# PowerSupply.net
KiCad netlist of a schematic drawn in Altium Designer
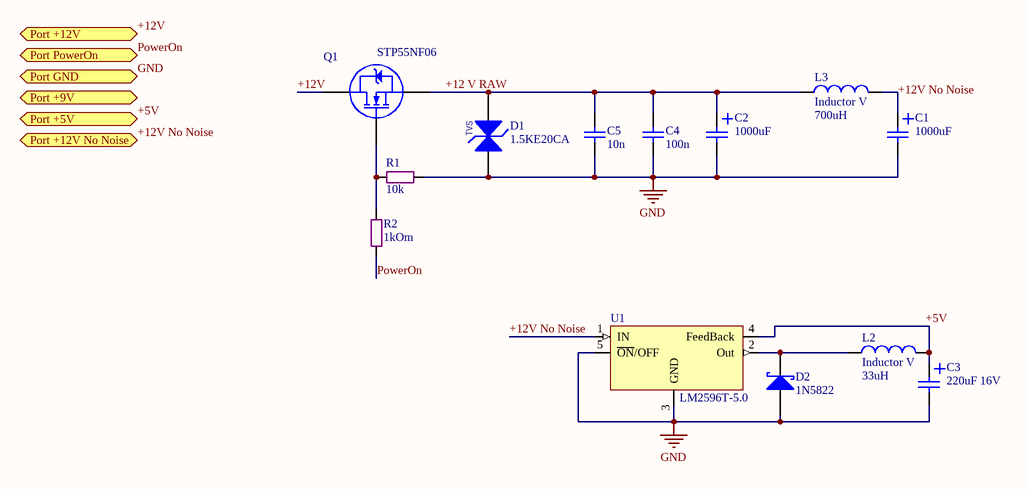
[diagram p0: PowerSupply.SchDoc]

(export (version "E")
  (design (tool "Eeschema 10.0.6"))
  (components
    (comp (ref "C1")
      (value "1000uF")
      (footprint "Capacitor:Cap E p5.08mm D10.2mm (3p)")
      (description "Capacitor")
      (libsource (lib "Capacitor") (part "Cap E 1000mF x 25V"))
    )
    (comp (ref "C2")
      (value "1000uF")
      (footprint "Capacitor:Cap E p5.08mm D10.2mm (3p)")
      (description "Capacitor")
      (libsource (lib "Capacitor") (part "Cap E 1000mF x 25V"))
    )
    (comp (ref "C3")
      (value "220uF 16V")
      (footprint "Capacitor:Cap E p2mm D6.5xH11")
      (description "Capacitor")
      (libsource (lib "Capacitor") (part "Cap E 220mF x 16V"))
    )
    (comp (ref "C4")
      (value "100n")
      (footprint "Capacitor:Cap P5.08MM (3p) disk2")
      (description "Capacitor")
      (libsource (lib "Capacitor") (part "Cap Ceramic"))
    )
    (comp (ref "C5")
      (value "10n")
      (footprint "Capacitor:Cap P5.08MM (3p) disk2")
      (description "Capacitor")
      (libsource (lib "Capacitor") (part "Cap Ceramic"))
    )
    (comp (ref "D1")
      (value "1.5KE20CA")
      (footprint "Diodes:TVS diode DO-201")
      (description "1500W Transil (TVS Diode)")
      (libsource (lib "Diodes") (part "TVS 1.5KE20CA"))
    )
    (comp (ref "D2")
      (value "1N5822")
      (footprint "Diodes:Diode DO-201")
      (description "3 Amp Shotki  Diode")
      (libsource (lib "Diodes") (part "D Shotki 1N5822"))
    )
    (comp (ref "L2")
      (value "Inductor V")
      (footprint "Transformers:Toroid V D14-W6")
      (description "Inductor Vertical")
      (fields (field (name "ALTIUM_VALUE") "33uH") (field (name "PUBLISHER") "Altium Limited"))
      (libsource (lib "Transformers") (part "Inductor V"))
    )
    (comp (ref "L3")
      (value "Inductor V")
      (footprint "Transformers:Toroid V D14-W6")
      (description "Inductor Vertical")
      (fields (field (name "ALTIUM_VALUE") "700uH") (field (name "PUBLISHER") "Altium Limited"))
      (libsource (lib "Transformers") (part "Inductor V"))
    )
    (comp (ref "Q1")
      (value "STP55NF06")
      (footprint "GeneralCases:TO220-2 Horisontal")
      (description "N-Channel 60V - 0.018Ω - 50A - D2PAK - I2PAK")
      (libsource (lib "Transistor") (part "STP55NF06"))
    )
    (comp (ref "R1")
      (value "10k")
      (footprint "SMD 0805 (2012)")
      (libsource (lib "PassiveComponents") (part "Res SMD 0805"))
    )
    (comp (ref "R2")
      (value "1kOm")
      (footprint "SMD 0805 (2012)")
      (libsource (lib "PassiveComponents") (part "Res SMD 0805"))
    )
    (comp (ref "U1")
      (value "LM2596T-5.0")
      (footprint "GeneralCases:TO220-5 Horisontal")
      (description "Voltage Regulator")
      (fields (field (name "MANUFACTURER") "National Semiconductor"))
      (libsource (lib "PowerAdjusment") (part "LM2596T-5.0"))
    )
  )
  (nets
    (net (code "1") (name "/+5V") (class "Default")
      (node (ref "C3") (pin "1") (pinfunction "1_1") (pintype "passive"))
      (node (ref "L2") (pin "2") (pinfunction "2_2") (pintype "passive"))
      (node (ref "U1") (pin "4") (pinfunction "FeedBack_4") (pintype "passive"))
    )
    (net (code "2") (name "/+12 V RAW") (class "Default")
      (node (ref "C2") (pin "1") (pinfunction "1_1") (pintype "passive"))
      (node (ref "C4") (pin "1") (pinfunction "1_1") (pintype "passive"))
      (node (ref "C5") (pin "1") (pinfunction "1_1") (pintype "passive"))
      (node (ref "D1") (pin "2") (pinfunction "2_2") (pintype "passive"))
      (node (ref "L3") (pin "1") (pinfunction "1_1") (pintype "passive"))
      (node (ref "Q1") (pin "3") (pinfunction "S_3") (pintype "passive"))
    )
    (net (code "3") (name "/+12V") (class "Default")
      (node (ref "Q1") (pin "2") (pinfunction "D_2") (pintype "passive"))
    )
    (net (code "4") (name "/+12V No Noise") (class "Default")
      (node (ref "C1") (pin "1") (pinfunction "1_1") (pintype "passive"))
      (node (ref "L3") (pin "2") (pinfunction "2_2") (pintype "passive"))
      (node (ref "U1") (pin "1") (pinfunction "IN_1") (pintype "input"))
    )
    (net (code "6") (name "/PowerOn") (class "Default")
      (node (ref "R2") (pin "1") (pinfunction "1_1") (pintype "passive"))
    )
    (net (code "7") (name "GND") (class "Default")
      (node (ref "C1") (pin "2") (pinfunction "2_2") (pintype "passive"))
      (node (ref "C2") (pin "2") (pinfunction "2_2") (pintype "passive"))
      (node (ref "C3") (pin "2") (pinfunction "2_2") (pintype "passive"))
      (node (ref "C4") (pin "2") (pinfunction "2_2") (pintype "passive"))
      (node (ref "C5") (pin "2") (pinfunction "2_2") (pintype "passive"))
      (node (ref "D1") (pin "1") (pinfunction "1_1") (pintype "passive"))
      (node (ref "D2") (pin "A") (pinfunction "A_A") (pintype "passive"))
      (node (ref "R1") (pin "2") (pinfunction "2_2") (pintype "passive"))
      (node (ref "U1") (pin "3") (pinfunction "GND_3") (pintype "passive"))
      (node (ref "U1") (pin "5") (pinfunction "~{ON}/OFF_5") (pintype "passive"))
    )
    (net (code "8") (name "Net-(Q1-G)") (class "Default")
      (node (ref "Q1") (pin "1") (pinfunction "G_1") (pintype "passive"))
      (node (ref "R1") (pin "1") (pinfunction "1_1") (pintype "passive"))
      (node (ref "R2") (pin "2") (pinfunction "2_2") (pintype "passive"))
    )
    (net (code "9") (name "Net-(U1-Out)") (class "Default")
      (node (ref "D2") (pin "K") (pinfunction "K_K") (pintype "passive"))
      (node (ref "L2") (pin "1") (pinfunction "1_1") (pintype "passive"))
      (node (ref "U1") (pin "2") (pinfunction "Out_2") (pintype "output"))
    )
  )
)
